# LPF-DAC.net
KiCad netlist of a schematic drawn in Altium Designer
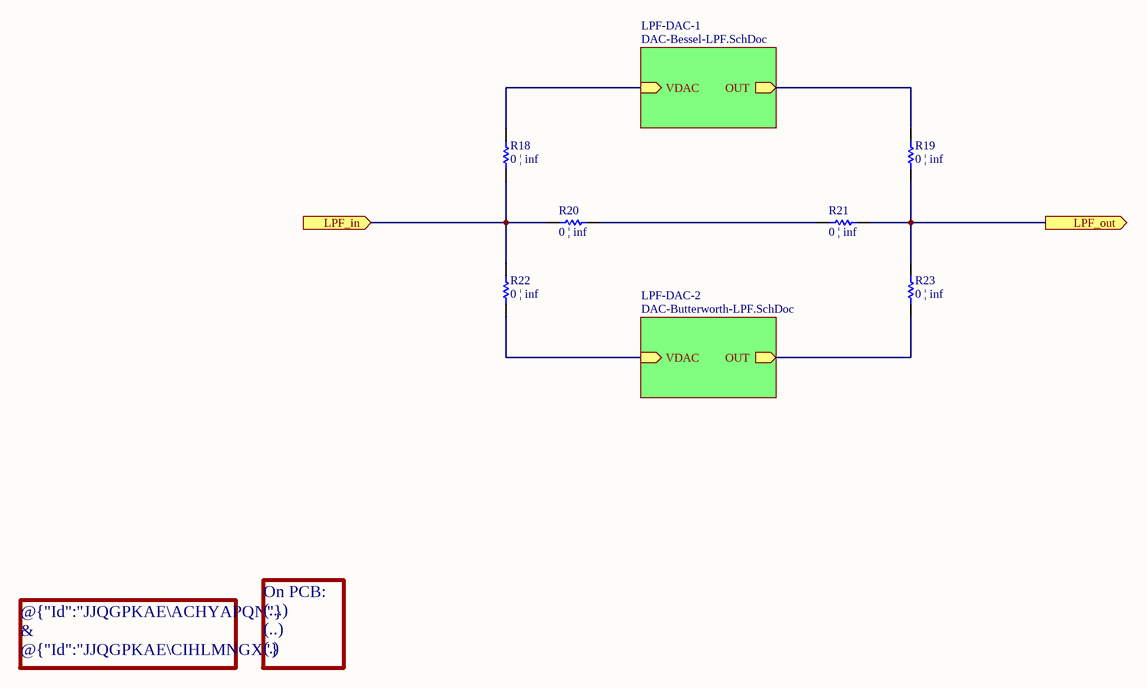
[diagram p0: LPF-DAC.SchDoc]

(export (version "E")
  (design (tool "Eeschema 10.0.6"))
  (components
    (comp (ref "R18") (value "0 ¦ inf") (footprint "RES_0402") (libsource (lib "IIS-Lib_TW") (part "Res")))
    (comp (ref "R19") (value "0 ¦ inf") (footprint "RES_0402") (libsource (lib "IIS-Lib_TW") (part "Res")))
    (comp (ref "R20") (value "0 ¦ inf") (footprint "RES_0402") (libsource (lib "IIS-Lib_TW") (part "Res")))
    (comp (ref "R21") (value "0 ¦ inf") (footprint "RES_0402") (libsource (lib "IIS-Lib_TW") (part "Res")))
    (comp (ref "R22") (value "0 ¦ inf") (footprint "RES_0402") (libsource (lib "IIS-Lib_TW") (part "Res")))
    (comp (ref "R23") (value "0 ¦ inf") (footprint "RES_0402") (libsource (lib "IIS-Lib_TW") (part "Res")))
  )
  (nets
    (net (code "1") (name "/LPF_in") (class "Default")
      (node (ref "R18") (pin "1") (pinfunction "1_1") (pintype "passive"))
      (node (ref "R20") (pin "2") (pinfunction "2_2") (pintype "passive"))
      (node (ref "R22") (pin "2") (pinfunction "2_2") (pintype "passive"))
    )
    (net (code "2") (name "/LPF_out") (class "Default")
      (node (ref "R19") (pin "1") (pinfunction "1_1") (pintype "passive"))
      (node (ref "R21") (pin "1") (pinfunction "1_1") (pintype "passive"))
      (node (ref "R23") (pin "2") (pinfunction "2_2") (pintype "passive"))
    )
    (net (code "3") (name "/OUT") (class "Default")
      (node (ref "R19") (pin "2") (pinfunction "2_2") (pintype "passive"))
    )
    (net (code "4") (name "/OUT_1") (class "Default")
      (node (ref "R23") (pin "1") (pinfunction "1_1") (pintype "passive"))
    )
    (net (code "5") (name "/VDAC") (class "Default")
      (node (ref "R18") (pin "2") (pinfunction "2_2") (pintype "passive"))
    )
    (net (code "6") (name "/VDAC_1") (class "Default")
      (node (ref "R22") (pin "1") (pinfunction "1_1") (pintype "passive"))
    )
    (net (code "7") (name "Net-(R20-Pad1)") (class "Default")
      (node (ref "R20") (pin "1") (pinfunction "1_1") (pintype "passive"))
      (node (ref "R21") (pin "2") (pinfunction "2_2") (pintype "passive"))
    )
  )
)
